# strip2.net
KiCad netlist of a schematic drawn in EAGLE
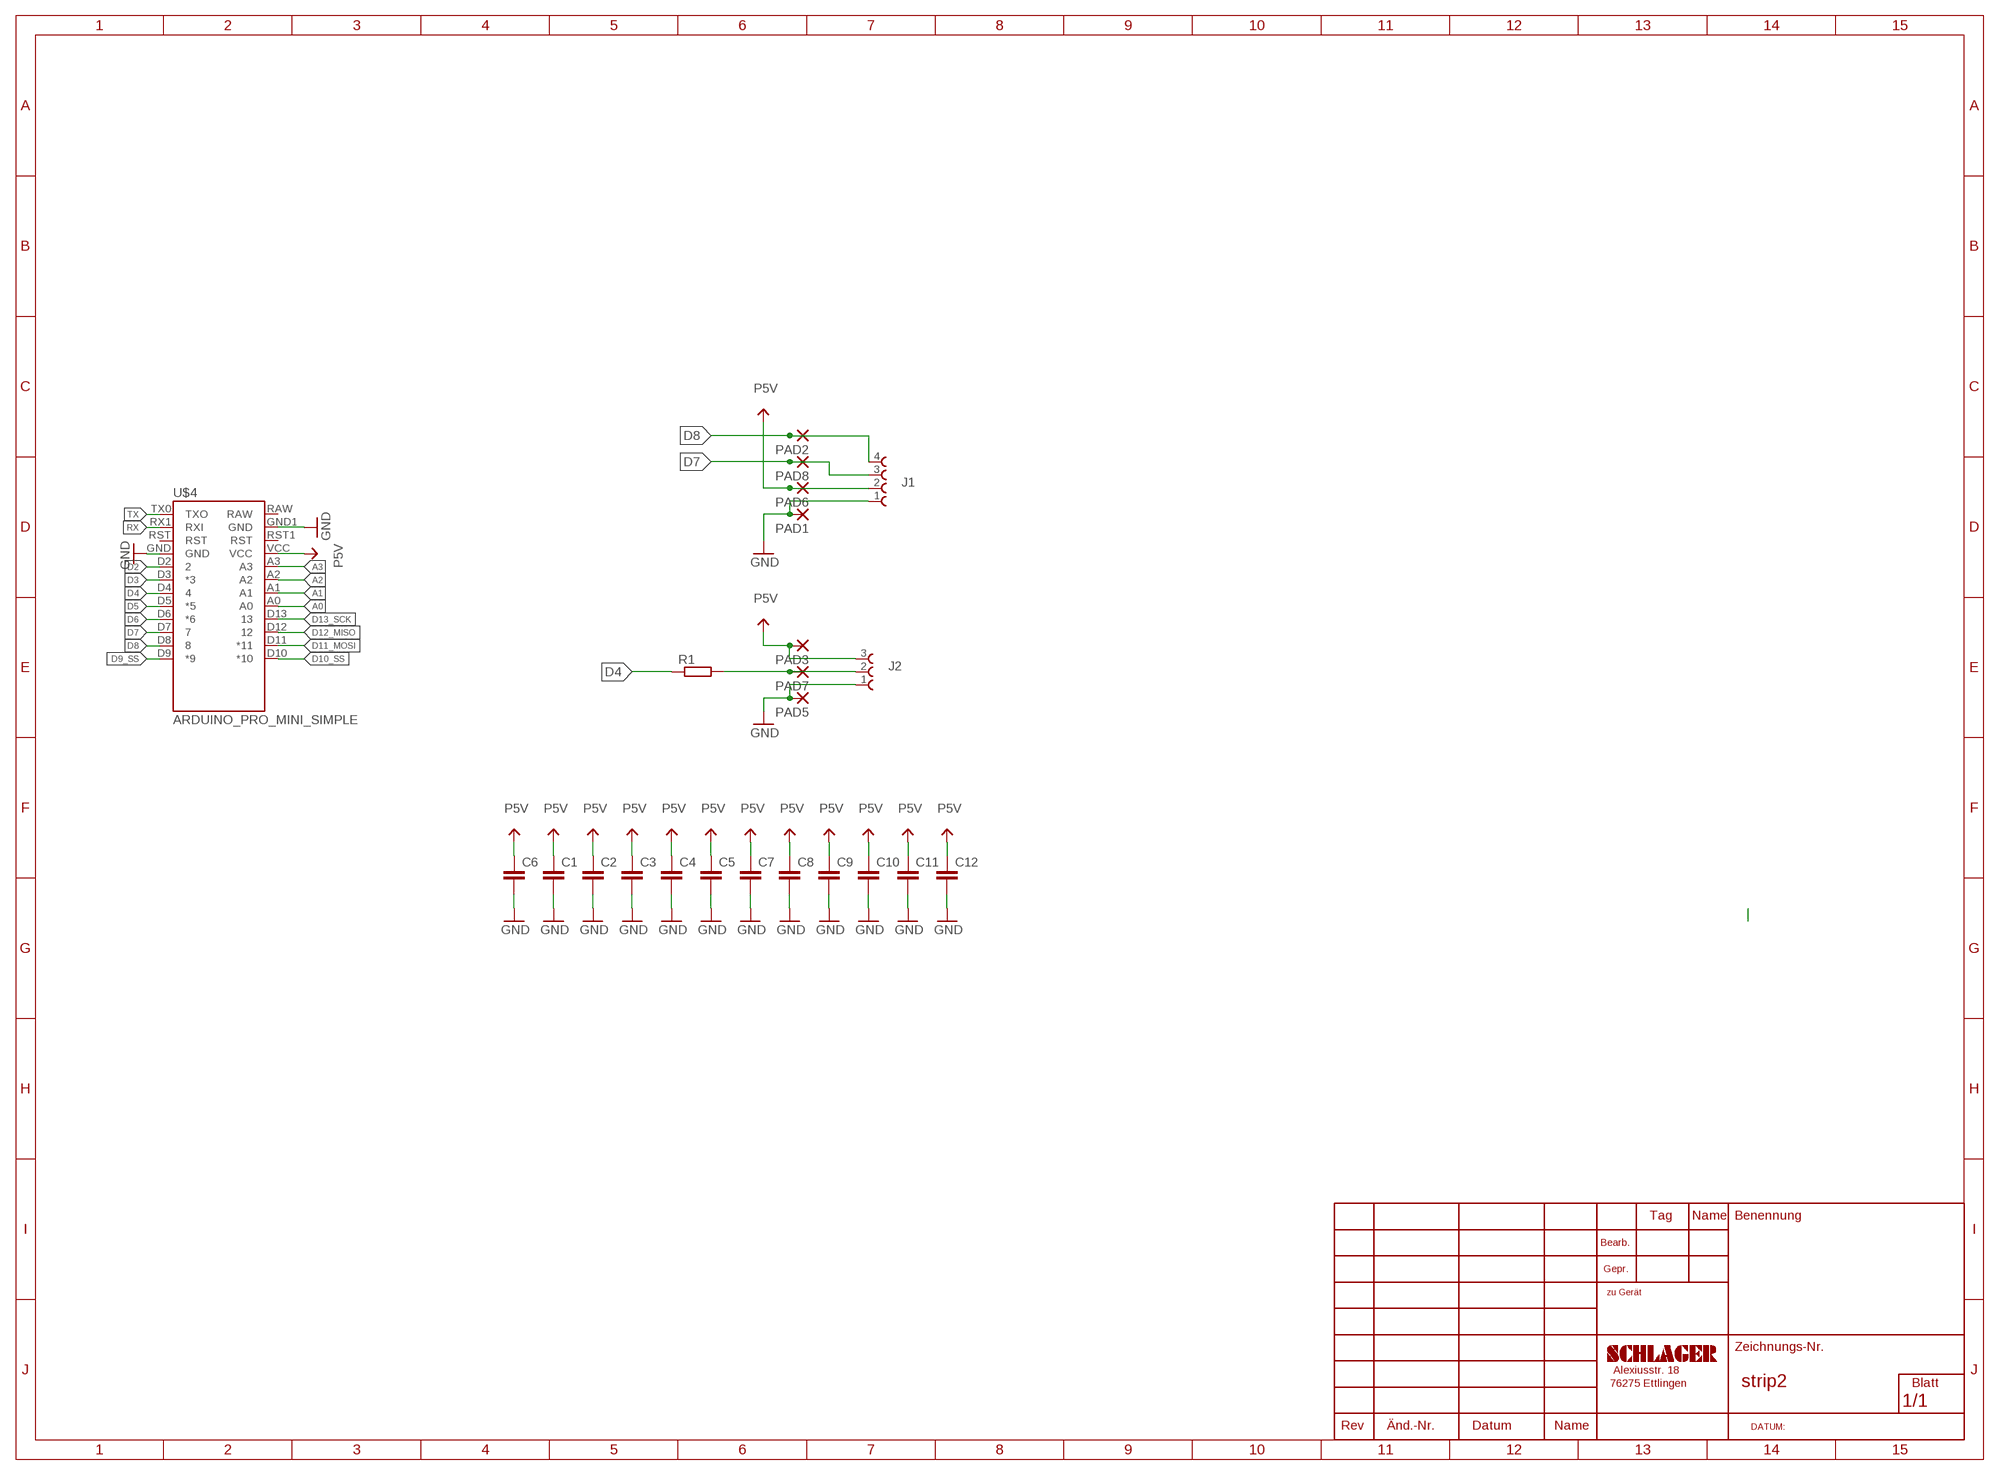
[diagram p0: schematic, sheet 1]

(export (version "E")
  (design (tool "Eeschema 10.0.6"))
  (components
    (comp (ref "C1")
      (value "C-EUC1210K")
      (footprint "eagle-import:C1210K")
      (libsource (lib "eagle-import") (part "C-EUC1210K"))
    )
    (comp (ref "C2")
      (value "C-EUC1210K")
      (footprint "eagle-import:C1210K")
      (libsource (lib "eagle-import") (part "C-EUC1210K"))
    )
    (comp (ref "C3")
      (value "C-EUC1210K")
      (footprint "eagle-import:C1210K")
      (libsource (lib "eagle-import") (part "C-EUC1210K"))
    )
    (comp (ref "C4")
      (value "C-EUC1210K")
      (footprint "eagle-import:C1210K")
      (libsource (lib "eagle-import") (part "C-EUC1210K"))
    )
    (comp (ref "C5")
      (value "C-EUC1210K")
      (footprint "eagle-import:C1210K")
      (libsource (lib "eagle-import") (part "C-EUC1210K"))
    )
    (comp (ref "C6")
      (value "C-EUC1210K")
      (footprint "eagle-import:C1210K")
      (libsource (lib "eagle-import") (part "C-EUC1210K"))
    )
    (comp (ref "C7")
      (value "C-EUC1206K")
      (footprint "eagle-import:C1206K")
      (libsource (lib "eagle-import") (part "C-EUC1206K"))
    )
    (comp (ref "C8")
      (value "C-EUC1206K")
      (footprint "eagle-import:C1206K")
      (libsource (lib "eagle-import") (part "C-EUC1206K"))
    )
    (comp (ref "C9")
      (value "C-EUC1206K")
      (footprint "eagle-import:C1206K")
      (libsource (lib "eagle-import") (part "C-EUC1206K"))
    )
    (comp (ref "C10")
      (value "C-EUC1206K")
      (footprint "eagle-import:C1206K")
      (libsource (lib "eagle-import") (part "C-EUC1206K"))
    )
    (comp (ref "C11")
      (value "C-EUC1206K")
      (footprint "eagle-import:C1206K")
      (libsource (lib "eagle-import") (part "C-EUC1206K"))
    )
    (comp (ref "C12")
      (value "C-EUC1206K")
      (footprint "eagle-import:C1206K")
      (libsource (lib "eagle-import") (part "C-EUC1206K"))
    )
    (comp (ref "J1")
      (value "691322110004")
      (footprint "eagle-import:691322110004")
      (libsource (lib "eagle-import") (part "691322110004"))
    )
    (comp (ref "J2")
      (value "691322110003")
      (footprint "eagle-import:691322110003")
      (libsource (lib "eagle-import") (part "691322110003"))
    )
    (comp (ref "PAD1")
      (value "SMD2")
      (footprint "eagle-import:SMD1,27-2,54")
      (libsource (lib "eagle-import") (part "SMD2"))
    )
    (comp (ref "PAD2")
      (value "SMD2")
      (footprint "eagle-import:SMD1,27-2,54")
      (libsource (lib "eagle-import") (part "SMD2"))
    )
    (comp (ref "PAD3")
      (value "SMD2")
      (footprint "eagle-import:SMD1,27-2,54")
      (libsource (lib "eagle-import") (part "SMD2"))
    )
    (comp (ref "PAD5")
      (value "SMD2")
      (footprint "eagle-import:SMD1,27-2,54")
      (libsource (lib "eagle-import") (part "SMD2"))
    )
    (comp (ref "PAD6")
      (value "SMD2")
      (footprint "eagle-import:SMD1,27-2,54")
      (libsource (lib "eagle-import") (part "SMD2"))
    )
    (comp (ref "PAD7")
      (value "SMD2")
      (footprint "eagle-import:SMD1,27-2,54")
      (libsource (lib "eagle-import") (part "SMD2"))
    )
    (comp (ref "PAD8")
      (value "SMD2")
      (footprint "eagle-import:SMD1,27-2,54")
      (libsource (lib "eagle-import") (part "SMD2"))
    )
    (comp (ref "R1")
      (value "R-EU_R0805")
      (footprint "eagle-import:R0805")
      (libsource (lib "eagle-import") (part "R-EU_R0805"))
    )
    (comp (ref "U$4")
      (value "ARDUINO_PRO_MINI_SIMPLE")
      (footprint "eagle-import:PRO_MINI_SIMPLE")
      (libsource (lib "eagle-import") (part "ARDUINO_PRO_MINI_SIMPLE"))
    )
  )
  (nets
    (net (code "1") (name "A0") (class "Default")
      (node (ref "U$4") (pin "A0") (pinfunction "A0_A0") (pintype "bidirectional"))
    )
    (net (code "2") (name "A1") (class "Default")
      (node (ref "U$4") (pin "A1") (pinfunction "A1_A1") (pintype "bidirectional"))
    )
    (net (code "3") (name "A2") (class "Default")
      (node (ref "U$4") (pin "A2") (pinfunction "A2_A2") (pintype "bidirectional"))
    )
    (net (code "4") (name "A3") (class "Default")
      (node (ref "U$4") (pin "A3") (pinfunction "A3_A3") (pintype "bidirectional"))
    )
    (net (code "5") (name "D2") (class "Default")
      (node (ref "U$4") (pin "D2") (pinfunction "2_D2") (pintype "bidirectional"))
    )
    (net (code "6") (name "D3") (class "Default")
      (node (ref "U$4") (pin "D3") (pinfunction "*3_D3") (pintype "bidirectional"))
    )
    (net (code "7") (name "D4") (class "Default")
      (node (ref "R1") (pin "1") (pinfunction "1_1") (pintype "passive"))
      (node (ref "U$4") (pin "D4") (pinfunction "4_D4") (pintype "bidirectional"))
    )
    (net (code "8") (name "D5") (class "Default")
      (node (ref "U$4") (pin "D5") (pinfunction "*5_D5") (pintype "bidirectional"))
    )
    (net (code "9") (name "D6") (class "Default")
      (node (ref "U$4") (pin "D6") (pinfunction "*6_D6") (pintype "bidirectional"))
    )
    (net (code "10") (name "D7") (class "Default")
      (node (ref "J1") (pin "3") (pinfunction "2_3") (pintype "passive"))
      (node (ref "PAD8") (pin "1") (pinfunction "P_1") (pintype "passive"))
      (node (ref "U$4") (pin "D7") (pinfunction "7_D7") (pintype "bidirectional"))
    )
    (net (code "11") (name "D8") (class "Default")
      (node (ref "J1") (pin "4") (pinfunction "1_4") (pintype "passive"))
      (node (ref "PAD2") (pin "1") (pinfunction "P_1") (pintype "passive"))
      (node (ref "U$4") (pin "D8") (pinfunction "8_D8") (pintype "bidirectional"))
    )
    (net (code "12") (name "D9_SS") (class "Default")
      (node (ref "U$4") (pin "D9") (pinfunction "*9_D9") (pintype "bidirectional"))
    )
    (net (code "13") (name "D10_SS") (class "Default")
      (node (ref "U$4") (pin "D10") (pinfunction "*10_D10") (pintype "bidirectional"))
    )
    (net (code "14") (name "D11_MOSI") (class "Default")
      (node (ref "U$4") (pin "D11") (pinfunction "*11_D11") (pintype "bidirectional"))
    )
    (net (code "15") (name "D12_MISO") (class "Default")
      (node (ref "U$4") (pin "D12") (pinfunction "12_D12") (pintype "bidirectional"))
    )
    (net (code "16") (name "D13_SCK") (class "Default")
      (node (ref "U$4") (pin "D13") (pinfunction "13_D13") (pintype "bidirectional"))
    )
    (net (code "17") (name "GND") (class "Default")
      (node (ref "C1") (pin "2") (pinfunction "2_2") (pintype "passive"))
      (node (ref "C10") (pin "2") (pinfunction "2_2") (pintype "passive"))
      (node (ref "C11") (pin "2") (pinfunction "2_2") (pintype "passive"))
      (node (ref "C12") (pin "2") (pinfunction "2_2") (pintype "passive"))
      (node (ref "C2") (pin "2") (pinfunction "2_2") (pintype "passive"))
      (node (ref "C3") (pin "2") (pinfunction "2_2") (pintype "passive"))
      (node (ref "C4") (pin "2") (pinfunction "2_2") (pintype "passive"))
      (node (ref "C5") (pin "2") (pinfunction "2_2") (pintype "passive"))
      (node (ref "C6") (pin "2") (pinfunction "2_2") (pintype "passive"))
      (node (ref "C7") (pin "2") (pinfunction "2_2") (pintype "passive"))
      (node (ref "C8") (pin "2") (pinfunction "2_2") (pintype "passive"))
      (node (ref "C9") (pin "2") (pinfunction "2_2") (pintype "passive"))
      (node (ref "J1") (pin "1") (pinfunction "4_1") (pintype "passive"))
      (node (ref "J2") (pin "1") (pinfunction "3_1") (pintype "passive"))
      (node (ref "PAD1") (pin "1") (pinfunction "P_1") (pintype "passive"))
      (node (ref "PAD5") (pin "1") (pinfunction "P_1") (pintype "passive"))
      (node (ref "U$4") (pin "GND") (pinfunction "GND_GND") (pintype "bidirectional"))
      (node (ref "U$4") (pin "GND1") (pinfunction "GND_GND1") (pintype "bidirectional"))
    )
    (net (code "18") (name "Net-(PAD7-P)") (class "Default")
      (node (ref "J2") (pin "2") (pinfunction "2_2") (pintype "passive"))
      (node (ref "PAD7") (pin "1") (pinfunction "P_1") (pintype "passive"))
      (node (ref "R1") (pin "2") (pinfunction "2_2") (pintype "passive"))
    )
    (net (code "19") (name "P5V") (class "Default")
      (node (ref "C1") (pin "1") (pinfunction "1_1") (pintype "passive"))
      (node (ref "C10") (pin "1") (pinfunction "1_1") (pintype "passive"))
      (node (ref "C11") (pin "1") (pinfunction "1_1") (pintype "passive"))
      (node (ref "C12") (pin "1") (pinfunction "1_1") (pintype "passive"))
      (node (ref "C2") (pin "1") (pinfunction "1_1") (pintype "passive"))
      (node (ref "C3") (pin "1") (pinfunction "1_1") (pintype "passive"))
      (node (ref "C4") (pin "1") (pinfunction "1_1") (pintype "passive"))
      (node (ref "C5") (pin "1") (pinfunction "1_1") (pintype "passive"))
      (node (ref "C6") (pin "1") (pinfunction "1_1") (pintype "passive"))
      (node (ref "C7") (pin "1") (pinfunction "1_1") (pintype "passive"))
      (node (ref "C8") (pin "1") (pinfunction "1_1") (pintype "passive"))
      (node (ref "C9") (pin "1") (pinfunction "1_1") (pintype "passive"))
      (node (ref "J1") (pin "2") (pinfunction "3_2") (pintype "passive"))
      (node (ref "J2") (pin "3") (pinfunction "1_3") (pintype "passive"))
      (node (ref "PAD3") (pin "1") (pinfunction "P_1") (pintype "passive"))
      (node (ref "PAD6") (pin "1") (pinfunction "P_1") (pintype "passive"))
      (node (ref "U$4") (pin "VCC") (pinfunction "VCC_VCC") (pintype "bidirectional"))
    )
    (net (code "20") (name "RX") (class "Default")
      (node (ref "U$4") (pin "RX1") (pinfunction "RXI_RX1") (pintype "bidirectional"))
    )
    (net (code "21") (name "TX") (class "Default")
      (node (ref "U$4") (pin "TX0") (pinfunction "TXO_TX0") (pintype "bidirectional"))
    )
    (net (code "22") (name "unconnected-(U$4-PadRAW)") (class "Default")
      (node (ref "U$4") (pin "RAW") (pinfunction "RAW_RAW") (pintype "bidirectional"))
    )
    (net (code "23") (name "unconnected-(U$4-PadRST)") (class "Default")
      (node (ref "U$4") (pin "RST") (pinfunction "RST_RST") (pintype "bidirectional"))
    )
    (net (code "24") (name "unconnected-(U$4-RST-PadRST1)") (class "Default")
      (node (ref "U$4") (pin "RST1") (pinfunction "RST_RST1") (pintype "bidirectional"))
    )
  )
)
